# Smart_Dustbin.net
KiCad netlist of a schematic drawn in Altium Designer
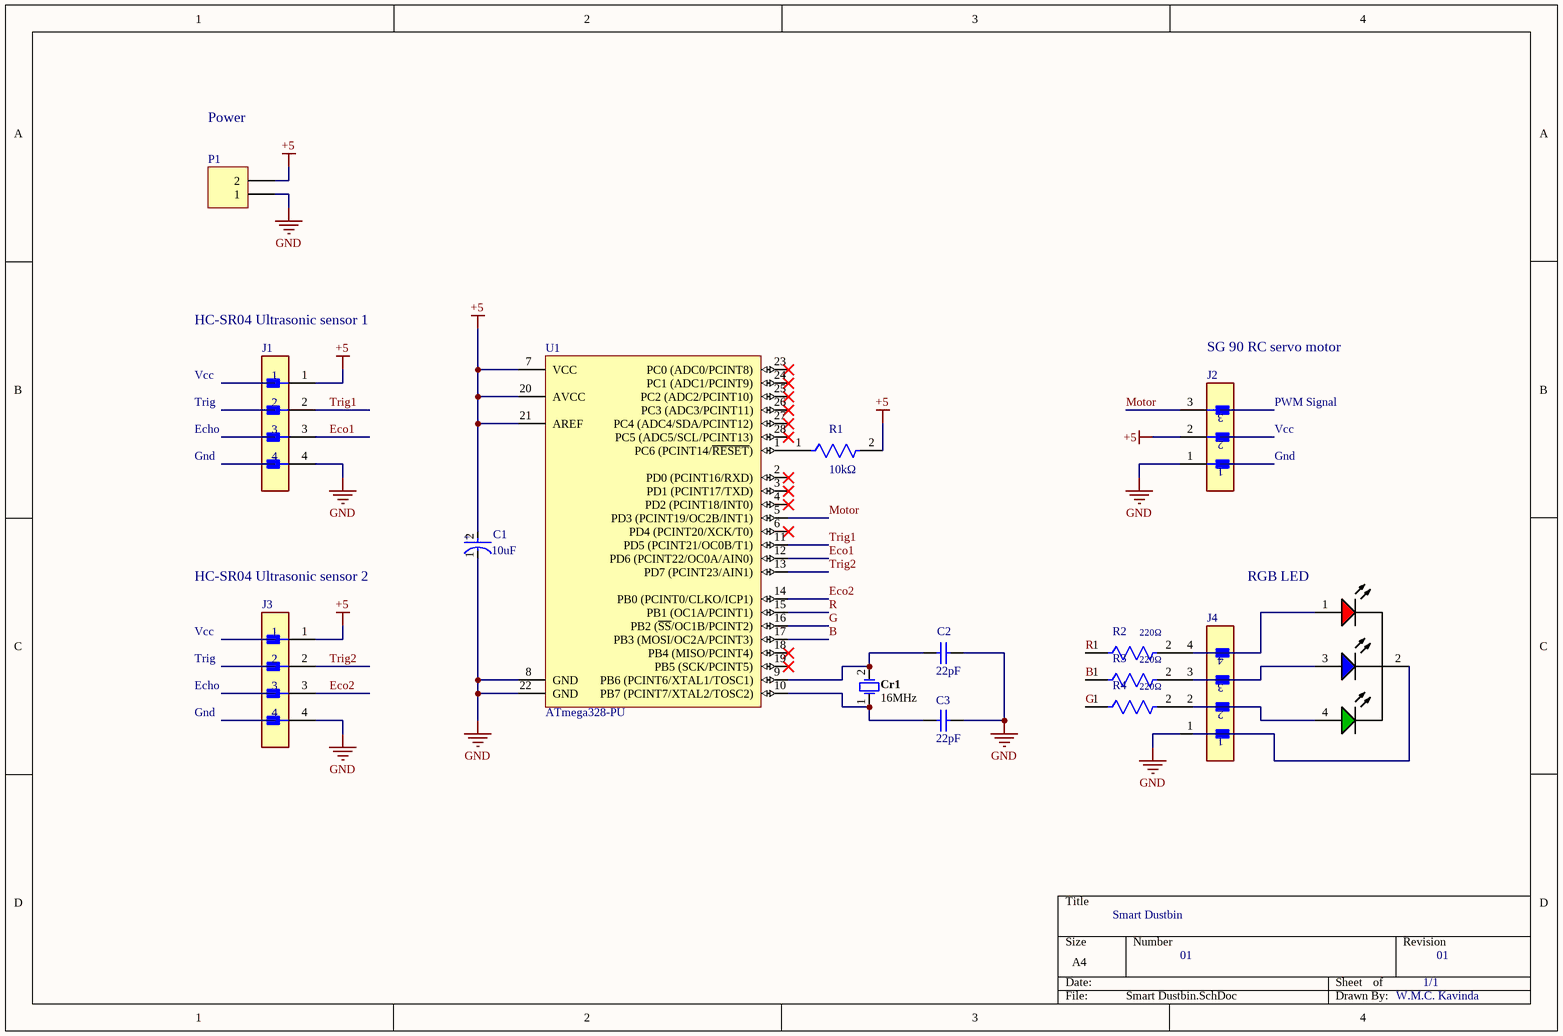
[diagram p0: Smart Dustbin.SchDoc]

(export (version "E")
  (design (tool "Eeschema 10.0.6"))
  (components
    (comp (ref "C1")
      (value "10uF")
      (footprint "FP-RAD-TH-D_8_0_5-L_11_5-MFG")
      (description "Aluminum Electrolytic Capacitors (Radial Lead Type) AEC-Q200 Qualified 10uF ±20% 50V")
      (fields (field (name "CAPACITANCE") "10uF") (field (name "TOLERANCE") "20%"))
      (libsource (lib "Altium Content Vault") (part "203bc49f2ac43e59fd269a8c329ed05"))
    )
    (comp (ref "C2")
      (value "22pF")
      (footprint "KEMT-C315-THT-2")
      (description "Capacitor, Ceramic, 22 pF, +/-10 %, 100 V, -55 to 125 degC, 2-Pin THD, RoHS, Bulk")
      (libsource (lib "Altium Content Vault") (part "CAP-NP-2"))
    )
    (comp (ref "C3")
      (value "22pF")
      (footprint "KEMT-C315-THT-2")
      (description "Capacitor, Ceramic, 22 pF, +/-10 %, 100 V, -55 to 125 degC, 2-Pin THD, RoHS, Bulk")
      (libsource (lib "Altium Content Vault") (part "CAP-NP-2"))
    )
    (comp (ref "Cr1")
      (value "16MHz")
      (footprint "FOX-FOXSLF160-20")
      (description "Resistance Weld Thru-Hole Crystal, 16 MHz, -20 to 70 degC, 2-Pin THD, RoHS, Bulk")
      (fields (field (name "TOLERANCE") "1%"))
      (libsource (lib "Altium Content Vault") (part "XTAL-1-2-2"))
    )
    (comp (ref "DS1")
      (value "WP154A4SUREQBFZGC")
      (footprint "KING-WP154A4SUREQBFZGC_V")
      (description "Full Color LED Lamp, Dominant Wavelength RGB 630 / 525 / 465 nm, -40 to 85 degC, 4-Pin THD, RoHS")
      (fields (field (name "MANUFACTURER") "Kingbright"))
      (libsource (lib "Altium Content Vault") (part "LED-RGB-AKAA-4"))
    )
    (comp (ref "J1")
      (value "TMM-104-01-S-S")
      (footprint "FP-TMM-104-01-S-S-MFG")
      (description "CONN HEADER VERT 4POS 2MM")
      (libsource (lib "Altium Content Vault") (part "299a8cea1bdcbc3624fe62c390fa72c"))
    )
    (comp (ref "J2")
      (value "TMM-103-03-T-S")
      (footprint "FP-TMM-103-03-T-S-MFG")
      (description "CONN HEADER VERT 3POS 2MM")
      (libsource (lib "Altium Content Vault") (part "0d3f023dd272f625e17a2be33dea85f"))
    )
    (comp (ref "J3")
      (value "TMM-104-01-S-S")
      (footprint "FP-TMM-104-01-S-S-MFG")
      (description "CONN HEADER VERT 4POS 2MM")
      (libsource (lib "Altium Content Vault") (part "299a8cea1bdcbc3624fe62c390fa72c"))
    )
    (comp (ref "J4")
      (value "TMM-104-01-S-S")
      (footprint "FP-TMM-104-01-S-S-MFG")
      (description "CONN HEADER VERT 4POS 2MM")
      (libsource (lib "") (part "299a8cea1bdcbc3624fe62c390fa72c_1"))
    )
    (comp (ref "P1")
      (value "Header 2")
      (footprint "HDR1X2")
      (description "Header, 2-Pin")
      (fields (field (name "PUBLISHER") "Altium Limited"))
      (libsource (lib "Miscellaneous Connectors") (part "Header 2"))
    )
    (comp (ref "R1")
      (value "10K")
      (footprint "FP-CF18-MFG")
      (description "RES 10K OHM 1/8W 5% CF AXIAL")
      (fields
        (field (name "MANUFACTURER PART NUMBER") "CF18JT10K0")
        (field (name "MANUFACTURER") "Stackpole Electronics")
        (field (name "RESISTANCE") "10kΩ")
      )
      (libsource (lib "Altium Content Vault") (part "1029c3af85768c4190bb7ad29bc67b5"))
    )
    (comp (ref "R2")
      (value "220Ω")
      (footprint "FP-MBA0204-MFG")
      (description "RES 220 OHM 0.4W 1% AXIAL")
      (fields
        (field (name "MANUFACTURER PART NUMBER") "MBA02040C2200FC100")
        (field (name "OCTOPART") "https://octopart.com/mba02040c2200fc100-vishay-43743094")
        (field (name "RESISTANCE") "220Ω")
      )
      (libsource (lib "Altium Content Vault") (part "1029c3af85768c4190bb7ad29bc67b5"))
    )
    (comp (ref "R3")
      (value "220Ω")
      (footprint "FP-MBA0204-MFG")
      (description "RES 220 OHM 0.4W 1% AXIAL")
      (fields
        (field (name "MANUFACTURER PART NUMBER") "MBA02040C2200FC100")
        (field (name "OCTOPART") "https://octopart.com/mba02040c2200fc100-vishay-43743094")
        (field (name "RESISTANCE") "220Ω")
      )
      (libsource (lib "Altium Content Vault") (part "1029c3af85768c4190bb7ad29bc67b5"))
    )
    (comp (ref "R4")
      (value "220Ω")
      (footprint "FP-MBA0204-MFG")
      (description "RES 220 OHM 0.4W 1% AXIAL")
      (fields
        (field (name "MANUFACTURER PART NUMBER") "MBA02040C2200FC100")
        (field (name "OCTOPART") "https://octopart.com/mba02040c2200fc100-vishay-43743094")
        (field (name "RESISTANCE") "220Ω")
      )
      (libsource (lib "Altium Content Vault") (part "1029c3af85768c4190bb7ad29bc67b5"))
    )
    (comp (ref "U1")
      (value "ATmega328-PU")
      (footprint "28P3")
      (libsource (lib "Altium Content Vault") (part "MC-8B-ATM48-IL28"))
    )
  )
  (nets
    (net (code "1") (name "+5") (class "Default")
      (node (ref "C1") (pin "2") (pinfunction "A_2") (pintype "passive"))
      (node (ref "J1") (pin "1") (pinfunction "1_1") (pintype "passive"))
      (node (ref "J2") (pin "2") (pinfunction "2_2") (pintype "passive"))
      (node (ref "J3") (pin "1") (pinfunction "1_1") (pintype "passive"))
      (node (ref "P1") (pin "2") (pinfunction "2_2") (pintype "passive"))
      (node (ref "R1") (pin "2") (pinfunction "2_2") (pintype "passive"))
      (node (ref "U1") (pin "20") (pinfunction "AVCC_20") (pintype "power_in"))
      (node (ref "U1") (pin "21") (pinfunction "AREF_21") (pintype "power_in"))
      (node (ref "U1") (pin "7") (pinfunction "VCC_7") (pintype "power_in"))
    )
    (net (code "2") (name "/B") (class "Default")
      (node (ref "R3") (pin "1") (pinfunction "1_1") (pintype "passive"))
      (node (ref "U1") (pin "17") (pinfunction "PB3_(MOSI/OC2A/PCINT3)_17") (pintype "bidirectional"))
    )
    (net (code "3") (name "/Eco1") (class "Default")
      (node (ref "J1") (pin "3") (pinfunction "3_3") (pintype "passive"))
      (node (ref "U1") (pin "12") (pinfunction "PD6_(PCINT22/OC0A/AIN0)_12") (pintype "bidirectional"))
    )
    (net (code "4") (name "/Eco2") (class "Default")
      (node (ref "J3") (pin "3") (pinfunction "3_3") (pintype "passive"))
      (node (ref "U1") (pin "14") (pinfunction "PB0_(PCINT0/CLKO/ICP1)_14") (pintype "bidirectional"))
    )
    (net (code "5") (name "/G") (class "Default")
      (node (ref "R4") (pin "1") (pinfunction "1_1") (pintype "passive"))
      (node (ref "U1") (pin "16") (pinfunction "PB2_(~{SS}/OC1B/PCINT2)_16") (pintype "bidirectional"))
    )
    (net (code "6") (name "/Motor") (class "Default")
      (node (ref "J2") (pin "3") (pinfunction "3_3") (pintype "passive"))
      (node (ref "U1") (pin "5") (pinfunction "PD3_(PCINT19/OC2B/INT1)_5") (pintype "bidirectional"))
    )
    (net (code "7") (name "/R") (class "Default")
      (node (ref "R2") (pin "1") (pinfunction "1_1") (pintype "passive"))
      (node (ref "U1") (pin "15") (pinfunction "PB1_(OC1A/PCINT1)_15") (pintype "bidirectional"))
    )
    (net (code "8") (name "/Trig1") (class "Default")
      (node (ref "J1") (pin "2") (pinfunction "2_2") (pintype "passive"))
      (node (ref "U1") (pin "11") (pinfunction "PD5_(PCINT21/OC0B/T1)_11") (pintype "bidirectional"))
    )
    (net (code "9") (name "/Trig2") (class "Default")
      (node (ref "J3") (pin "2") (pinfunction "2_2") (pintype "passive"))
      (node (ref "U1") (pin "13") (pinfunction "PD7_(PCINT23/AIN1)_13") (pintype "bidirectional"))
    )
    (net (code "10") (name "GND") (class "Default")
      (node (ref "C1") (pin "1") (pinfunction "C_1") (pintype "passive"))
      (node (ref "C2") (pin "2") (pinfunction "2_2") (pintype "passive"))
      (node (ref "C3") (pin "2") (pinfunction "2_2") (pintype "passive"))
      (node (ref "J1") (pin "4") (pinfunction "4_4") (pintype "passive"))
      (node (ref "J2") (pin "1") (pinfunction "1_1") (pintype "passive"))
      (node (ref "J3") (pin "4") (pinfunction "4_4") (pintype "passive"))
      (node (ref "J4") (pin "1") (pinfunction "1_1") (pintype "passive"))
      (node (ref "P1") (pin "1") (pinfunction "1_1") (pintype "passive"))
      (node (ref "U1") (pin "22") (pinfunction "GND_22") (pintype "power_in"))
      (node (ref "U1") (pin "8") (pinfunction "GND_8") (pintype "power_in"))
    )
    (net (code "11") (name "Net-(J4-Pad2)") (class "Default")
      (node (ref "J4") (pin "2") (pinfunction "2_2") (pintype "passive"))
      (node (ref "R4") (pin "2") (pinfunction "2_2") (pintype "passive"))
    )
    (net (code "12") (name "Net-(J4-Pad3)") (class "Default")
      (node (ref "J4") (pin "3") (pinfunction "3_3") (pintype "passive"))
      (node (ref "R3") (pin "2") (pinfunction "2_2") (pintype "passive"))
    )
    (net (code "13") (name "Net-(J4-Pad4)") (class "Default")
      (node (ref "J4") (pin "4") (pinfunction "4_4") (pintype "passive"))
      (node (ref "R2") (pin "2") (pinfunction "2_2") (pintype "passive"))
    )
    (net (code "14") (name "Net-(U1-PB6_(PCINT6{slash}XTAL1{slash}TOSC1))") (class "Default")
      (node (ref "C2") (pin "1") (pinfunction "1_1") (pintype "passive"))
      (node (ref "Cr1") (pin "2") (pinfunction "2_2") (pintype "passive"))
      (node (ref "U1") (pin "9") (pinfunction "PB6_(PCINT6/XTAL1/TOSC1)_9") (pintype "bidirectional"))
    )
    (net (code "15") (name "Net-(U1-PB7_(PCINT7{slash}XTAL2{slash}TOSC2))") (class "Default")
      (node (ref "C3") (pin "1") (pinfunction "1_1") (pintype "passive"))
      (node (ref "Cr1") (pin "1") (pinfunction "1_1") (pintype "passive"))
      (node (ref "U1") (pin "10") (pinfunction "PB7_(PCINT7/XTAL2/TOSC2)_10") (pintype "bidirectional"))
    )
    (net (code "16") (name "Net-(U1-PC6_(PCINT14{slash}~{RESET}))") (class "Default")
      (node (ref "R1") (pin "1") (pinfunction "1_1") (pintype "passive"))
      (node (ref "U1") (pin "1") (pinfunction "PC6_(PCINT14/~{RESET})_1") (pintype "bidirectional"))
    )
    (net (code "17") (name "unconnected-(DS1-BLUE-Pad3)") (class "Default")
      (node (ref "DS1") (pin "3") (pinfunction "BLUE_3") (pintype "passive"))
    )
    (net (code "18") (name "unconnected-(DS1-CATHODE-Pad2)") (class "Default")
      (node (ref "DS1") (pin "2") (pinfunction "CATHODE_2") (pintype "passive"))
    )
    (net (code "19") (name "unconnected-(DS1-GREEN-Pad4)") (class "Default")
      (node (ref "DS1") (pin "4") (pinfunction "GREEN_4") (pintype "passive"))
    )
    (net (code "20") (name "unconnected-(DS1-RED-Pad1)") (class "Default")
      (node (ref "DS1") (pin "1") (pinfunction "RED_1") (pintype "passive"))
    )
    (net (code "21") (name "unconnected-(U1-PB4_(MISO{slash}PCINT4)-Pad18)") (class "Default")
      (node (ref "U1") (pin "18") (pinfunction "PB4_(MISO/PCINT4)_18") (pintype "bidirectional+no_connect"))
    )
    (net (code "22") (name "unconnected-(U1-PB5_(SCK{slash}PCINT5)-Pad19)") (class "Default")
      (node (ref "U1") (pin "19") (pinfunction "PB5_(SCK/PCINT5)_19") (pintype "bidirectional+no_connect"))
    )
    (net (code "23") (name "unconnected-(U1-PC0_(ADC0{slash}PCINT8)-Pad23)") (class "Default")
      (node (ref "U1") (pin "23") (pinfunction "PC0_(ADC0/PCINT8)_23") (pintype "bidirectional+no_connect"))
    )
    (net (code "24") (name "unconnected-(U1-PC1_(ADC1{slash}PCINT9)-Pad24)") (class "Default")
      (node (ref "U1") (pin "24") (pinfunction "PC1_(ADC1/PCINT9)_24") (pintype "bidirectional+no_connect"))
    )
    (net (code "25") (name "unconnected-(U1-PC2_(ADC2{slash}PCINT10)-Pad25)") (class "Default")
      (node (ref "U1") (pin "25") (pinfunction "PC2_(ADC2/PCINT10)_25") (pintype "bidirectional+no_connect"))
    )
    (net (code "26") (name "unconnected-(U1-PC3_(ADC3{slash}PCINT11)-Pad26)") (class "Default")
      (node (ref "U1") (pin "26") (pinfunction "PC3_(ADC3/PCINT11)_26") (pintype "bidirectional+no_connect"))
    )
    (net (code "27") (name "unconnected-(U1-PC4_(ADC4{slash}SDA{slash}PCINT12)-Pad27)") (class "Default")
      (node (ref "U1") (pin "27") (pinfunction "PC4_(ADC4/SDA/PCINT12)_27") (pintype "bidirectional+no_connect"))
    )
    (net (code "28") (name "unconnected-(U1-PC5_(ADC5{slash}SCL{slash}PCINT13)-Pad28)") (class "Default")
      (node (ref "U1") (pin "28") (pinfunction "PC5_(ADC5/SCL/PCINT13)_28") (pintype "bidirectional+no_connect"))
    )
    (net (code "29") (name "unconnected-(U1-PD0_(PCINT16{slash}RXD)-Pad2)") (class "Default")
      (node (ref "U1") (pin "2") (pinfunction "PD0_(PCINT16/RXD)_2") (pintype "bidirectional+no_connect"))
    )
    (net (code "30") (name "unconnected-(U1-PD1_(PCINT17{slash}TXD)-Pad3)") (class "Default")
      (node (ref "U1") (pin "3") (pinfunction "PD1_(PCINT17/TXD)_3") (pintype "bidirectional+no_connect"))
    )
    (net (code "31") (name "unconnected-(U1-PD2_(PCINT18{slash}INT0)-Pad4)") (class "Default")
      (node (ref "U1") (pin "4") (pinfunction "PD2_(PCINT18/INT0)_4") (pintype "bidirectional+no_connect"))
    )
    (net (code "32") (name "unconnected-(U1-PD4_(PCINT20{slash}XCK{slash}T0)-Pad6)") (class "Default")
      (node (ref "U1") (pin "6") (pinfunction "PD4_(PCINT20/XCK/T0)_6") (pintype "bidirectional+no_connect"))
    )
  )
)
